# Power_Section.net
KiCad netlist of a schematic drawn in Altium Designer
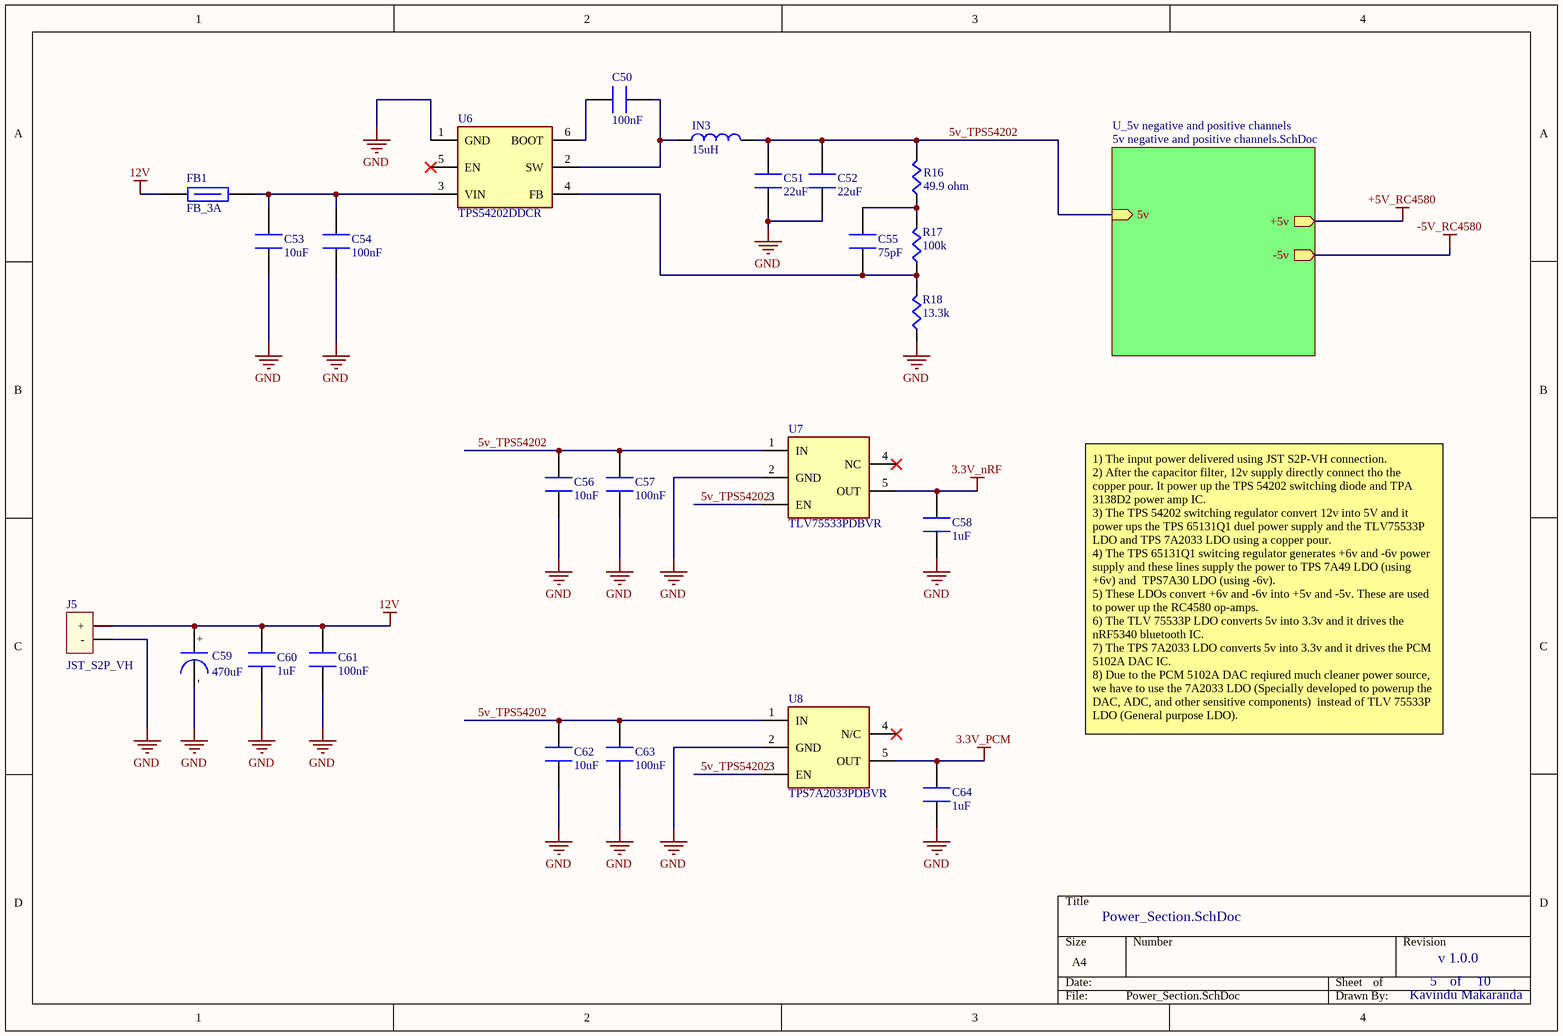
[diagram p0: Power_Section.SchDoc]

(export (version "E")
  (design (tool "Eeschema 10.0.6"))
  (components
    (comp (ref "C50")
      (value "100nF")
      (footprint "CAPC0603X8N")
      (libsource (lib "Schlib1") (part "CC0603_100nF_X7R"))
    )
    (comp (ref "C51")
      (value "22uF")
      (footprint "CAPC1210X25N")
      (description "C309062, CL32B226KAJNNNE, 22uF 25V X7R ±10% 1210 Multilayer Ceramic Capacitors MLCC - SMD/SMT ROHS")
      (libsource (lib "Schlib1") (part "CC1210_22uF_X7R"))
    )
    (comp (ref "C52")
      (value "22uF")
      (footprint "CAPC1210X25N")
      (description "C309062, CL32B226KAJNNNE, 22uF 25V X7R ±10% 1210 Multilayer Ceramic Capacitors MLCC - SMD/SMT ROHS")
      (libsource (lib "Schlib1") (part "CC1210_22uF_X7R"))
    )
    (comp (ref "C53")
      (value "10uF")
      (footprint "CAPC0805X14N")
      (description "C95841, CL21B106KOQNNNE, 10uF 16V X7R ±10% 0805 Multilayer Ceramic Capacitors MLCC - SMD/SMT ROHS")
      (libsource (lib "Schlib1") (part "CC0805_10uF_X7R"))
    )
    (comp (ref "C54")
      (value "100nF")
      (footprint "CAPC0603X8N")
      (libsource (lib "Schlib1") (part "CC0603_100nF_X7R"))
    )
    (comp (ref "C55")
      (value "75pF")
      (footprint "CAPC0603X8N")
      (libsource (lib "Schlib1") (part "CC0603_75pF_NPO"))
    )
    (comp (ref "C56")
      (value "10uF")
      (footprint "CAPC0805X14N")
      (description "C95841, CL21B106KOQNNNE, 10uF 16V X7R ±10% 0805 Multilayer Ceramic Capacitors MLCC - SMD/SMT ROHS")
      (libsource (lib "Schlib1") (part "CC0805_10uF_X7R"))
    )
    (comp (ref "C57")
      (value "100nF")
      (footprint "CAPC0603X8N")
      (libsource (lib "Schlib1") (part "CC0603_100nF_X7R"))
    )
    (comp (ref "C58")
      (value "1uF")
      (footprint "CAP0805X13N")
      (description "C28323, CL21B105KBFNNNE, 1uF 50V X7R ±10% 0805 Multilayer Ceramic Capacitors MLCC - SMD/SMT ROHS")
      (libsource (lib "Schlib1") (part "CC0805_1uF_X7R"))
    )
    (comp (ref "C59")
      (value "470uF")
      (footprint "CAPD10XL11.1X10.2M")
      (libsource (lib "Schlib1") (part "CPD10XL10.2_470uF_ALUM"))
    )
    (comp (ref "C60")
      (value "1uF")
      (footprint "CAP0805X13N")
      (description "C28323, CL21B105KBFNNNE, 1uF 50V X7R ±10% 0805 Multilayer Ceramic Capacitors MLCC - SMD/SMT ROHS")
      (libsource (lib "Schlib1") (part "CC0805_1uF_X7R"))
    )
    (comp (ref "C61")
      (value "100nF")
      (footprint "CAPC0603X8N")
      (libsource (lib "Schlib1") (part "CC0603_100nF_X7R"))
    )
    (comp (ref "C62")
      (value "10uF")
      (footprint "CAPC0805X14N")
      (description "C95841, CL21B106KOQNNNE, 10uF 16V X7R ±10% 0805 Multilayer Ceramic Capacitors MLCC - SMD/SMT ROHS")
      (libsource (lib "Schlib1") (part "CC0805_10uF_X7R"))
    )
    (comp (ref "C63")
      (value "100nF")
      (footprint "CAPC0603X8N")
      (libsource (lib "Schlib1") (part "CC0603_100nF_X7R"))
    )
    (comp (ref "C64")
      (value "1uF")
      (footprint "CAP0805X13N")
      (description "C28323, CL21B105KBFNNNE, 1uF 50V X7R ±10% 0805 Multilayer Ceramic Capacitors MLCC - SMD/SMT ROHS")
      (libsource (lib "Schlib1") (part "CC0805_1uF_X7R"))
    )
    (comp (ref "FB1")
      (value "FB_3A")
      (footprint "FB0603X08N")
      (description "C107332, MPZ1608S101ATAH0, -55℃~+125℃ 1 100Ω@100MHz 30mΩ 3A ±25% 0603 Ferrite Beads ROHS")
      (libsource (lib "Schlib1") (part "FB0603_3A"))
    )
    (comp (ref "IN3")
      (value "15uH")
      (footprint "INDM7266X30N")
      (description "C5189959, CYA0630-15UH, 15uH 3.8A 3A 98mΩ ±20% SMD,7.2x6.6mm Inductors (SMD) ROHS")
      (libsource (lib "Schlib1") (part "IN7266_15uH_3A"))
    )
    (comp (ref "J5")
      (value "JST_S2P_VH")
      (footprint "JST_S2P_VH")
      (libsource (lib "Schlib1") (part "JST_S2P_VH"))
    )
    (comp (ref "R16")
      (value "49.9 ohm")
      (footprint "RECS0603X45N")
      (libsource (lib "Schlib1") (part "RESC0603_49.9_THIN"))
    )
    (comp (ref "R17")
      (value "100k")
      (footprint "RECS0603X45N")
      (libsource (lib "Schlib1") (part "RESC0603_100K_THIN"))
    )
    (comp (ref "R18")
      (value "13.3k")
      (footprint "RECS0603X45N")
      (libsource (lib "Schlib1") (part "REC0603_13.3K_THICK"))
    )
    (comp (ref "U6")
      (value "TPS54202DDCR")
      (footprint "TPS54202DDCR")
      (fields (field (name "MOUSER PART NUMBER") "595-TPS54202DDCR"))
      (libsource (lib "Schlib1") (part "TPS54202DDCR"))
    )
    (comp (ref "U7")
      (value "TLV75533PDBVR")
      (footprint "SOT95P280X145-5N")
      (fields (field (name "MOUSER PART NUMBER") "595-TLV75533PDBVR"))
      (libsource (lib "Schlib1") (part "TLV75533PDBVR"))
    )
    (comp (ref "U8")
      (value "TPS7A2033PDBVR")
      (footprint "SOT95P280X145-5N")
      (fields (field (name "MOUSER PART NUMBER") "595-TPS7A2033PDBVR"))
      (libsource (lib "Schlib1") (part "TPS7A2033PDBVR"))
    )
  )
  (nets
    (net (code "3") (name "/5v_TPS54202") (class "Default")
      (node (ref "C51") (pin "2") (pinfunction "2_2") (pintype "passive"))
      (node (ref "C52") (pin "2") (pinfunction "2_2") (pintype "passive"))
      (node (ref "C56") (pin "2") (pinfunction "2_2") (pintype "passive"))
      (node (ref "C57") (pin "2") (pinfunction "2_2") (pintype "passive"))
      (node (ref "C62") (pin "2") (pinfunction "2_2") (pintype "passive"))
      (node (ref "C63") (pin "2") (pinfunction "2_2") (pintype "passive"))
      (node (ref "IN3") (pin "2") (pinfunction "2_2") (pintype "passive"))
      (node (ref "R16") (pin "2") (pinfunction "2_2") (pintype "passive"))
      (node (ref "U7") (pin "1") (pinfunction "IN_1") (pintype "passive"))
      (node (ref "U7") (pin "3") (pinfunction "EN_3") (pintype "passive"))
      (node (ref "U8") (pin "1") (pinfunction "IN_1") (pintype "passive"))
      (node (ref "U8") (pin "3") (pinfunction "EN_3") (pintype "passive"))
    )
    (net (code "4") (name "3.3V_PCM") (class "Default")
      (node (ref "C64") (pin "2") (pinfunction "2_2") (pintype "passive"))
      (node (ref "U8") (pin "5") (pinfunction "OUT_5") (pintype "passive"))
    )
    (net (code "5") (name "3.3V_nRF") (class "Default")
      (node (ref "C58") (pin "2") (pinfunction "2_2") (pintype "passive"))
      (node (ref "U7") (pin "5") (pinfunction "OUT_5") (pintype "passive"))
    )
    (net (code "6") (name "12V") (class "Default")
      (node (ref "C59") (pin "1") (pinfunction "1_1") (pintype "passive"))
      (node (ref "C60") (pin "2") (pinfunction "2_2") (pintype "passive"))
      (node (ref "C61") (pin "2") (pinfunction "2_2") (pintype "passive"))
      (node (ref "FB1") (pin "1") (pinfunction "1_1") (pintype "passive"))
      (node (ref "J5") (pin "1") (pinfunction "+_1") (pintype "passive"))
    )
    (net (code "7") (name "GND") (class "Default")
      (node (ref "C51") (pin "1") (pinfunction "1_1") (pintype "passive"))
      (node (ref "C52") (pin "1") (pinfunction "1_1") (pintype "passive"))
      (node (ref "C53") (pin "1") (pinfunction "1_1") (pintype "passive"))
      (node (ref "C54") (pin "1") (pinfunction "1_1") (pintype "passive"))
      (node (ref "C56") (pin "1") (pinfunction "1_1") (pintype "passive"))
      (node (ref "C57") (pin "1") (pinfunction "1_1") (pintype "passive"))
      (node (ref "C58") (pin "1") (pinfunction "1_1") (pintype "passive"))
      (node (ref "C59") (pin "2") (pinfunction "2_2") (pintype "passive"))
      (node (ref "C60") (pin "1") (pinfunction "1_1") (pintype "passive"))
      (node (ref "C61") (pin "1") (pinfunction "1_1") (pintype "passive"))
      (node (ref "C62") (pin "1") (pinfunction "1_1") (pintype "passive"))
      (node (ref "C63") (pin "1") (pinfunction "1_1") (pintype "passive"))
      (node (ref "C64") (pin "1") (pinfunction "1_1") (pintype "passive"))
      (node (ref "J5") (pin "2") (pinfunction "-_2") (pintype "passive"))
      (node (ref "R18") (pin "1") (pinfunction "1_1") (pintype "passive"))
      (node (ref "U6") (pin "1") (pinfunction "GND_1") (pintype "power_in"))
      (node (ref "U7") (pin "2") (pinfunction "GND_2") (pintype "passive"))
      (node (ref "U8") (pin "2") (pinfunction "GND_2") (pintype "passive"))
    )
    (net (code "8") (name "Net-(C55-Pad2)") (class "Default")
      (node (ref "C55") (pin "2") (pinfunction "2_2") (pintype "passive"))
      (node (ref "R16") (pin "1") (pinfunction "1_1") (pintype "passive"))
      (node (ref "R17") (pin "2") (pinfunction "2_2") (pintype "passive"))
    )
    (net (code "9") (name "Net-(U6-BOOT)") (class "Default")
      (node (ref "C50") (pin "2") (pinfunction "2_2") (pintype "passive"))
      (node (ref "U6") (pin "6") (pinfunction "BOOT_6") (pintype "passive"))
    )
    (net (code "10") (name "Net-(U6-FB)") (class "Default")
      (node (ref "C55") (pin "1") (pinfunction "1_1") (pintype "passive"))
      (node (ref "R17") (pin "1") (pinfunction "1_1") (pintype "passive"))
      (node (ref "R18") (pin "2") (pinfunction "2_2") (pintype "passive"))
      (node (ref "U6") (pin "4") (pinfunction "FB_4") (pintype "passive"))
    )
    (net (code "11") (name "Net-(U6-SW)") (class "Default")
      (node (ref "C50") (pin "1") (pinfunction "1_1") (pintype "passive"))
      (node (ref "IN3") (pin "1") (pinfunction "1_1") (pintype "passive"))
      (node (ref "U6") (pin "2") (pinfunction "SW_2") (pintype "passive"))
    )
    (net (code "12") (name "Net-(U6-VIN)") (class "Default")
      (node (ref "C53") (pin "2") (pinfunction "2_2") (pintype "passive"))
      (node (ref "C54") (pin "2") (pinfunction "2_2") (pintype "passive"))
      (node (ref "FB1") (pin "2") (pinfunction "2_2") (pintype "passive"))
      (node (ref "U6") (pin "3") (pinfunction "VIN_3") (pintype "power_in"))
    )
    (net (code "13") (name "unconnected-(U6-EN-Pad5)") (class "Default")
      (node (ref "U6") (pin "5") (pinfunction "EN_5") (pintype "passive+no_connect"))
    )
    (net (code "14") (name "unconnected-(U7-NC-Pad4)") (class "Default")
      (node (ref "U7") (pin "4") (pinfunction "NC_4") (pintype "passive+no_connect"))
    )
    (net (code "15") (name "unconnected-(U8-N{slash}C-Pad4)") (class "Default")
      (node (ref "U8") (pin "4") (pinfunction "N/C_4") (pintype "passive+no_connect"))
    )
  )
)
